# nrf-v1.net
KiCad netlist of a schematic drawn in EAGLE
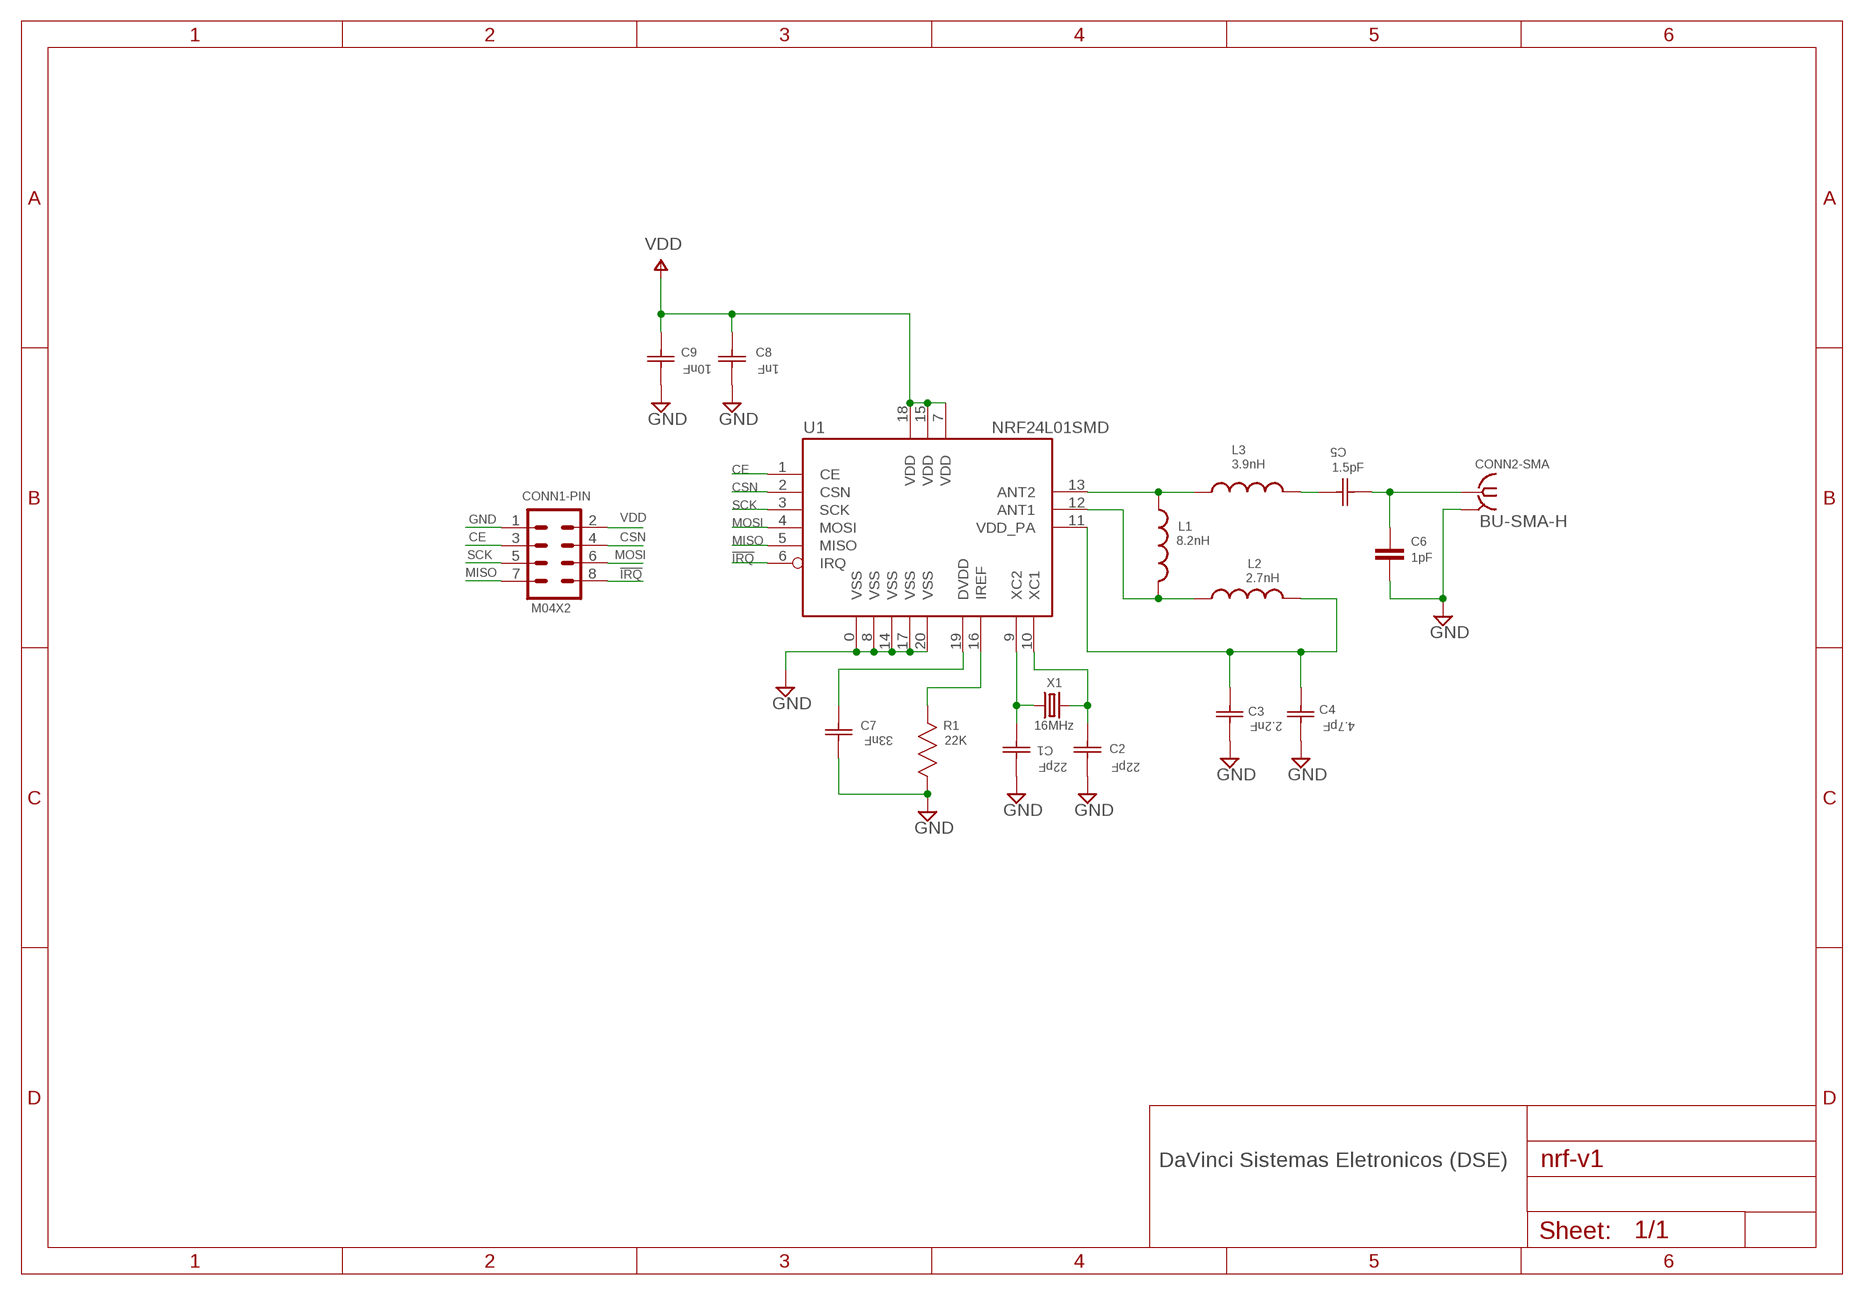
[diagram p0: schematic, sheet 1]

(export (version "E")
  (design (tool "Eeschema 10.0.6"))
  (components
    (comp (ref "C1")
      (value "22pF")
      (footprint "eagle-import:CAPC1005X60N")
      (fields (field (name "MPN") "UQCL2A220JAT2A/500") (field (name "TOLERANCE") "±5%"))
      (libsource (lib "eagle-import") (part "UQCL2A220JAT2A/500"))
    )
    (comp (ref "C2")
      (value "22pF")
      (footprint "eagle-import:CAPC1005X60N")
      (fields (field (name "MPN") "UQCL2A220JAT2A/500") (field (name "TOLERANCE") "±5%"))
      (libsource (lib "eagle-import") (part "UQCL2A220JAT2A/500"))
    )
    (comp (ref "C3")
      (value "2.2nF")
      (footprint "eagle-import:CAPC1005X60N")
      (fields (field (name "MPN") "UQCL2A220JAT2A/500") (field (name "TOLERANCE") "±5%"))
      (libsource (lib "eagle-import") (part "UQCL2A220JAT2A/500"))
    )
    (comp (ref "C4")
      (value "4.7pF")
      (footprint "eagle-import:CAPC1005X60N")
      (fields (field (name "MPN") "UQCL2A220JAT2A/500") (field (name "TOLERANCE") "±5%"))
      (libsource (lib "eagle-import") (part "UQCL2A220JAT2A/500"))
    )
    (comp (ref "C5")
      (value "1.5pF")
      (footprint "eagle-import:CAPC1005X60N")
      (fields (field (name "MPN") "UQCL2A220JAT2A/500") (field (name "TOLERANCE") "±5%"))
      (libsource (lib "eagle-import") (part "UQCL2A220JAT2A/500"))
    )
    (comp (ref "C6")
      (value "1pF")
      (footprint "eagle-import:C01005")
      (libsource (lib "eagle-import") (part "C-EU01005"))
    )
    (comp (ref "C7")
      (value "33nF")
      (footprint "eagle-import:CAPC1005X60N")
      (fields (field (name "MPN") "UQCL2A220JAT2A/500") (field (name "TOLERANCE") "±5%"))
      (libsource (lib "eagle-import") (part "UQCL2A220JAT2A/500"))
    )
    (comp (ref "C8")
      (value "1nF")
      (footprint "eagle-import:CAPC1005X60N")
      (fields (field (name "MPN") "UQCL2A220JAT2A/500") (field (name "TOLERANCE") "±5%"))
      (libsource (lib "eagle-import") (part "UQCL2A220JAT2A/500"))
    )
    (comp (ref "C9")
      (value "10nF")
      (footprint "eagle-import:CAPC1005X60N")
      (fields (field (name "MPN") "UQCL2A220JAT2A/500") (field (name "TOLERANCE") "±5%"))
      (libsource (lib "eagle-import") (part "UQCL2A220JAT2A/500"))
    )
    (comp (ref "CONN1-PIN")
      (value "M04X2")
      (footprint "eagle-import:2X4")
      (libsource (lib "eagle-import") (part "M04X2"))
    )
    (comp (ref "CONN2-SMA")
      (value "BU-SMA-H")
      (footprint "eagle-import:BU-SMA-H")
      (libsource (lib "eagle-import") (part "BU-SMA-H"))
    )
    (comp (ref "L1")
      (value "8.2nH")
      (footprint "eagle-import:C0402")
      (libsource (lib "eagle-import") (part "INDUCTOR0402"))
    )
    (comp (ref "L2")
      (value "2.7nH")
      (footprint "eagle-import:C0402")
      (libsource (lib "eagle-import") (part "INDUCTOR0402"))
    )
    (comp (ref "L3")
      (value "3.9nH")
      (footprint "eagle-import:C0402")
      (libsource (lib "eagle-import") (part "INDUCTOR0402"))
    )
    (comp (ref "R1")
      (value "22K")
      (footprint "eagle-import:RESC1005X40N")
      (fields (field (name "MPN") "TNPW040220K0BEED") (field (name "TOLERANCE") "± 0.1 %"))
      (libsource (lib "eagle-import") (part "TNPW040220K0BEED"))
    )
    (comp (ref "U1")
      (value "NRF24L01SMD")
      (footprint "eagle-import:QFN20")
      (libsource (lib "eagle-import") (part "NRF24L01SMD"))
    )
    (comp (ref "X1")
      (value "16MHz")
      (footprint "eagle-import:CRYSTAL-TXC-7A")
      (libsource (lib "eagle-import") (part "CRYSTALTXC-7A"))
    )
  )
  (nets
    (net (code "1") (name "/CE") (class "Default")
      (node (ref "CONN1-PIN") (pin "3") (pinfunction "3_3") (pintype "passive"))
      (node (ref "U1") (pin "1") (pinfunction "CE_1") (pintype "input"))
    )
    (net (code "2") (name "/CSN") (class "Default")
      (node (ref "CONN1-PIN") (pin "4") (pinfunction "4_4") (pintype "passive"))
      (node (ref "U1") (pin "2") (pinfunction "CSN_2") (pintype "input"))
    )
    (net (code "3") (name "/MISO") (class "Default")
      (node (ref "CONN1-PIN") (pin "7") (pinfunction "7_7") (pintype "passive"))
      (node (ref "U1") (pin "5") (pinfunction "MISO_5") (pintype "output"))
    )
    (net (code "4") (name "/MOSI") (class "Default")
      (node (ref "CONN1-PIN") (pin "6") (pinfunction "6_6") (pintype "passive"))
      (node (ref "U1") (pin "4") (pinfunction "MOSI_4") (pintype "input"))
    )
    (net (code "5") (name "/SCK") (class "Default")
      (node (ref "CONN1-PIN") (pin "5") (pinfunction "5_5") (pintype "passive"))
      (node (ref "U1") (pin "3") (pinfunction "SCK_3") (pintype "input"))
    )
    (net (code "6") (name "/~{IRQ}") (class "Default")
      (node (ref "CONN1-PIN") (pin "8") (pinfunction "8_8") (pintype "passive"))
      (node (ref "U1") (pin "6") (pinfunction "IRQ_6") (pintype "output"))
    )
    (net (code "7") (name "GND") (class "Default")
      (node (ref "C1") (pin "2") (pinfunction "C1_2") (pintype "passive"))
      (node (ref "C2") (pin "2") (pinfunction "C1_2") (pintype "passive"))
      (node (ref "C3") (pin "2") (pinfunction "C1_2") (pintype "passive"))
      (node (ref "C4") (pin "2") (pinfunction "C1_2") (pintype "passive"))
      (node (ref "C6") (pin "2") (pinfunction "2_2") (pintype "passive"))
      (node (ref "C7") (pin "2") (pinfunction "C1_2") (pintype "passive"))
      (node (ref "C8") (pin "2") (pinfunction "C1_2") (pintype "passive"))
      (node (ref "C9") (pin "2") (pinfunction "C1_2") (pintype "passive"))
      (node (ref "CONN1-PIN") (pin "1") (pinfunction "1_1") (pintype "passive"))
      (node (ref "CONN2-SMA") (pin "2") (pinfunction "2_2") (pintype "passive"))
      (node (ref "CONN2-SMA") (pin "3") (pinfunction "2_3") (pintype "passive"))
      (node (ref "CONN2-SMA") (pin "4") (pinfunction "2_4") (pintype "passive"))
      (node (ref "CONN2-SMA") (pin "5") (pinfunction "2_5") (pintype "passive"))
      (node (ref "R1") (pin "1") (pinfunction "1_1") (pintype "passive"))
      (node (ref "U1") (pin "0") (pinfunction "VSS_0") (pintype "power_in"))
      (node (ref "U1") (pin "14") (pinfunction "VSS_14") (pintype "power_in"))
      (node (ref "U1") (pin "17") (pinfunction "VSS_17") (pintype "power_in"))
      (node (ref "U1") (pin "20") (pinfunction "VSS_20") (pintype "power_in"))
      (node (ref "U1") (pin "8") (pinfunction "VSS_8") (pintype "power_in"))
    )
    (net (code "8") (name "Net-(C1-C2)") (class "Default")
      (node (ref "C1") (pin "1") (pinfunction "C2_1") (pintype "passive"))
      (node (ref "U1") (pin "9") (pinfunction "XC2_9") (pintype "input"))
      (node (ref "X1") (pin "P$1") (pinfunction "1_P$1") (pintype "passive"))
    )
    (net (code "9") (name "Net-(C2-C2)") (class "Default")
      (node (ref "C2") (pin "1") (pinfunction "C2_1") (pintype "passive"))
      (node (ref "U1") (pin "10") (pinfunction "XC1_10") (pintype "input"))
      (node (ref "X1") (pin "P$2") (pinfunction "2_P$2") (pintype "passive"))
    )
    (net (code "10") (name "Net-(C3-C2)") (class "Default")
      (node (ref "C3") (pin "1") (pinfunction "C2_1") (pintype "passive"))
      (node (ref "C4") (pin "1") (pinfunction "C2_1") (pintype "passive"))
      (node (ref "L2") (pin "2") (pinfunction "2_2") (pintype "passive"))
      (node (ref "U1") (pin "11") (pinfunction "VDD_PA_11") (pintype "power_in"))
    )
    (net (code "11") (name "Net-(C5-C1)") (class "Default")
      (node (ref "C5") (pin "2") (pinfunction "C1_2") (pintype "passive"))
      (node (ref "C6") (pin "1") (pinfunction "1_1") (pintype "passive"))
      (node (ref "CONN2-SMA") (pin "1") (pinfunction "1_1") (pintype "passive"))
    )
    (net (code "12") (name "Net-(C5-C2)") (class "Default")
      (node (ref "C5") (pin "1") (pinfunction "C2_1") (pintype "passive"))
      (node (ref "L3") (pin "2") (pinfunction "2_2") (pintype "passive"))
    )
    (net (code "13") (name "Net-(C7-C2)") (class "Default")
      (node (ref "C7") (pin "1") (pinfunction "C2_1") (pintype "passive"))
      (node (ref "U1") (pin "19") (pinfunction "DVDD_19") (pintype "power_in"))
    )
    (net (code "14") (name "Net-(U1-ANT1)") (class "Default")
      (node (ref "L1") (pin "2") (pinfunction "2_2") (pintype "passive"))
      (node (ref "L2") (pin "1") (pinfunction "1_1") (pintype "passive"))
      (node (ref "U1") (pin "12") (pinfunction "ANT1_12") (pintype "output"))
    )
    (net (code "15") (name "Net-(U1-ANT2)") (class "Default")
      (node (ref "L1") (pin "1") (pinfunction "1_1") (pintype "passive"))
      (node (ref "L3") (pin "1") (pinfunction "1_1") (pintype "passive"))
      (node (ref "U1") (pin "13") (pinfunction "ANT2_13") (pintype "output"))
    )
    (net (code "16") (name "Net-(U1-IREF)") (class "Default")
      (node (ref "R1") (pin "2") (pinfunction "2_2") (pintype "passive"))
      (node (ref "U1") (pin "16") (pinfunction "IREF_16") (pintype "input"))
    )
    (net (code "17") (name "VDD") (class "Default")
      (node (ref "C8") (pin "1") (pinfunction "C2_1") (pintype "passive"))
      (node (ref "C9") (pin "1") (pinfunction "C2_1") (pintype "passive"))
      (node (ref "CONN1-PIN") (pin "2") (pinfunction "2_2") (pintype "passive"))
      (node (ref "U1") (pin "15") (pinfunction "VDD_15") (pintype "power_in"))
      (node (ref "U1") (pin "18") (pinfunction "VDD_18") (pintype "power_in"))
      (node (ref "U1") (pin "7") (pinfunction "VDD_7") (pintype "power_in"))
    )
  )
)
